# xen_teensy_controls_template.net
KiCad netlist of a schematic drawn in EAGLE
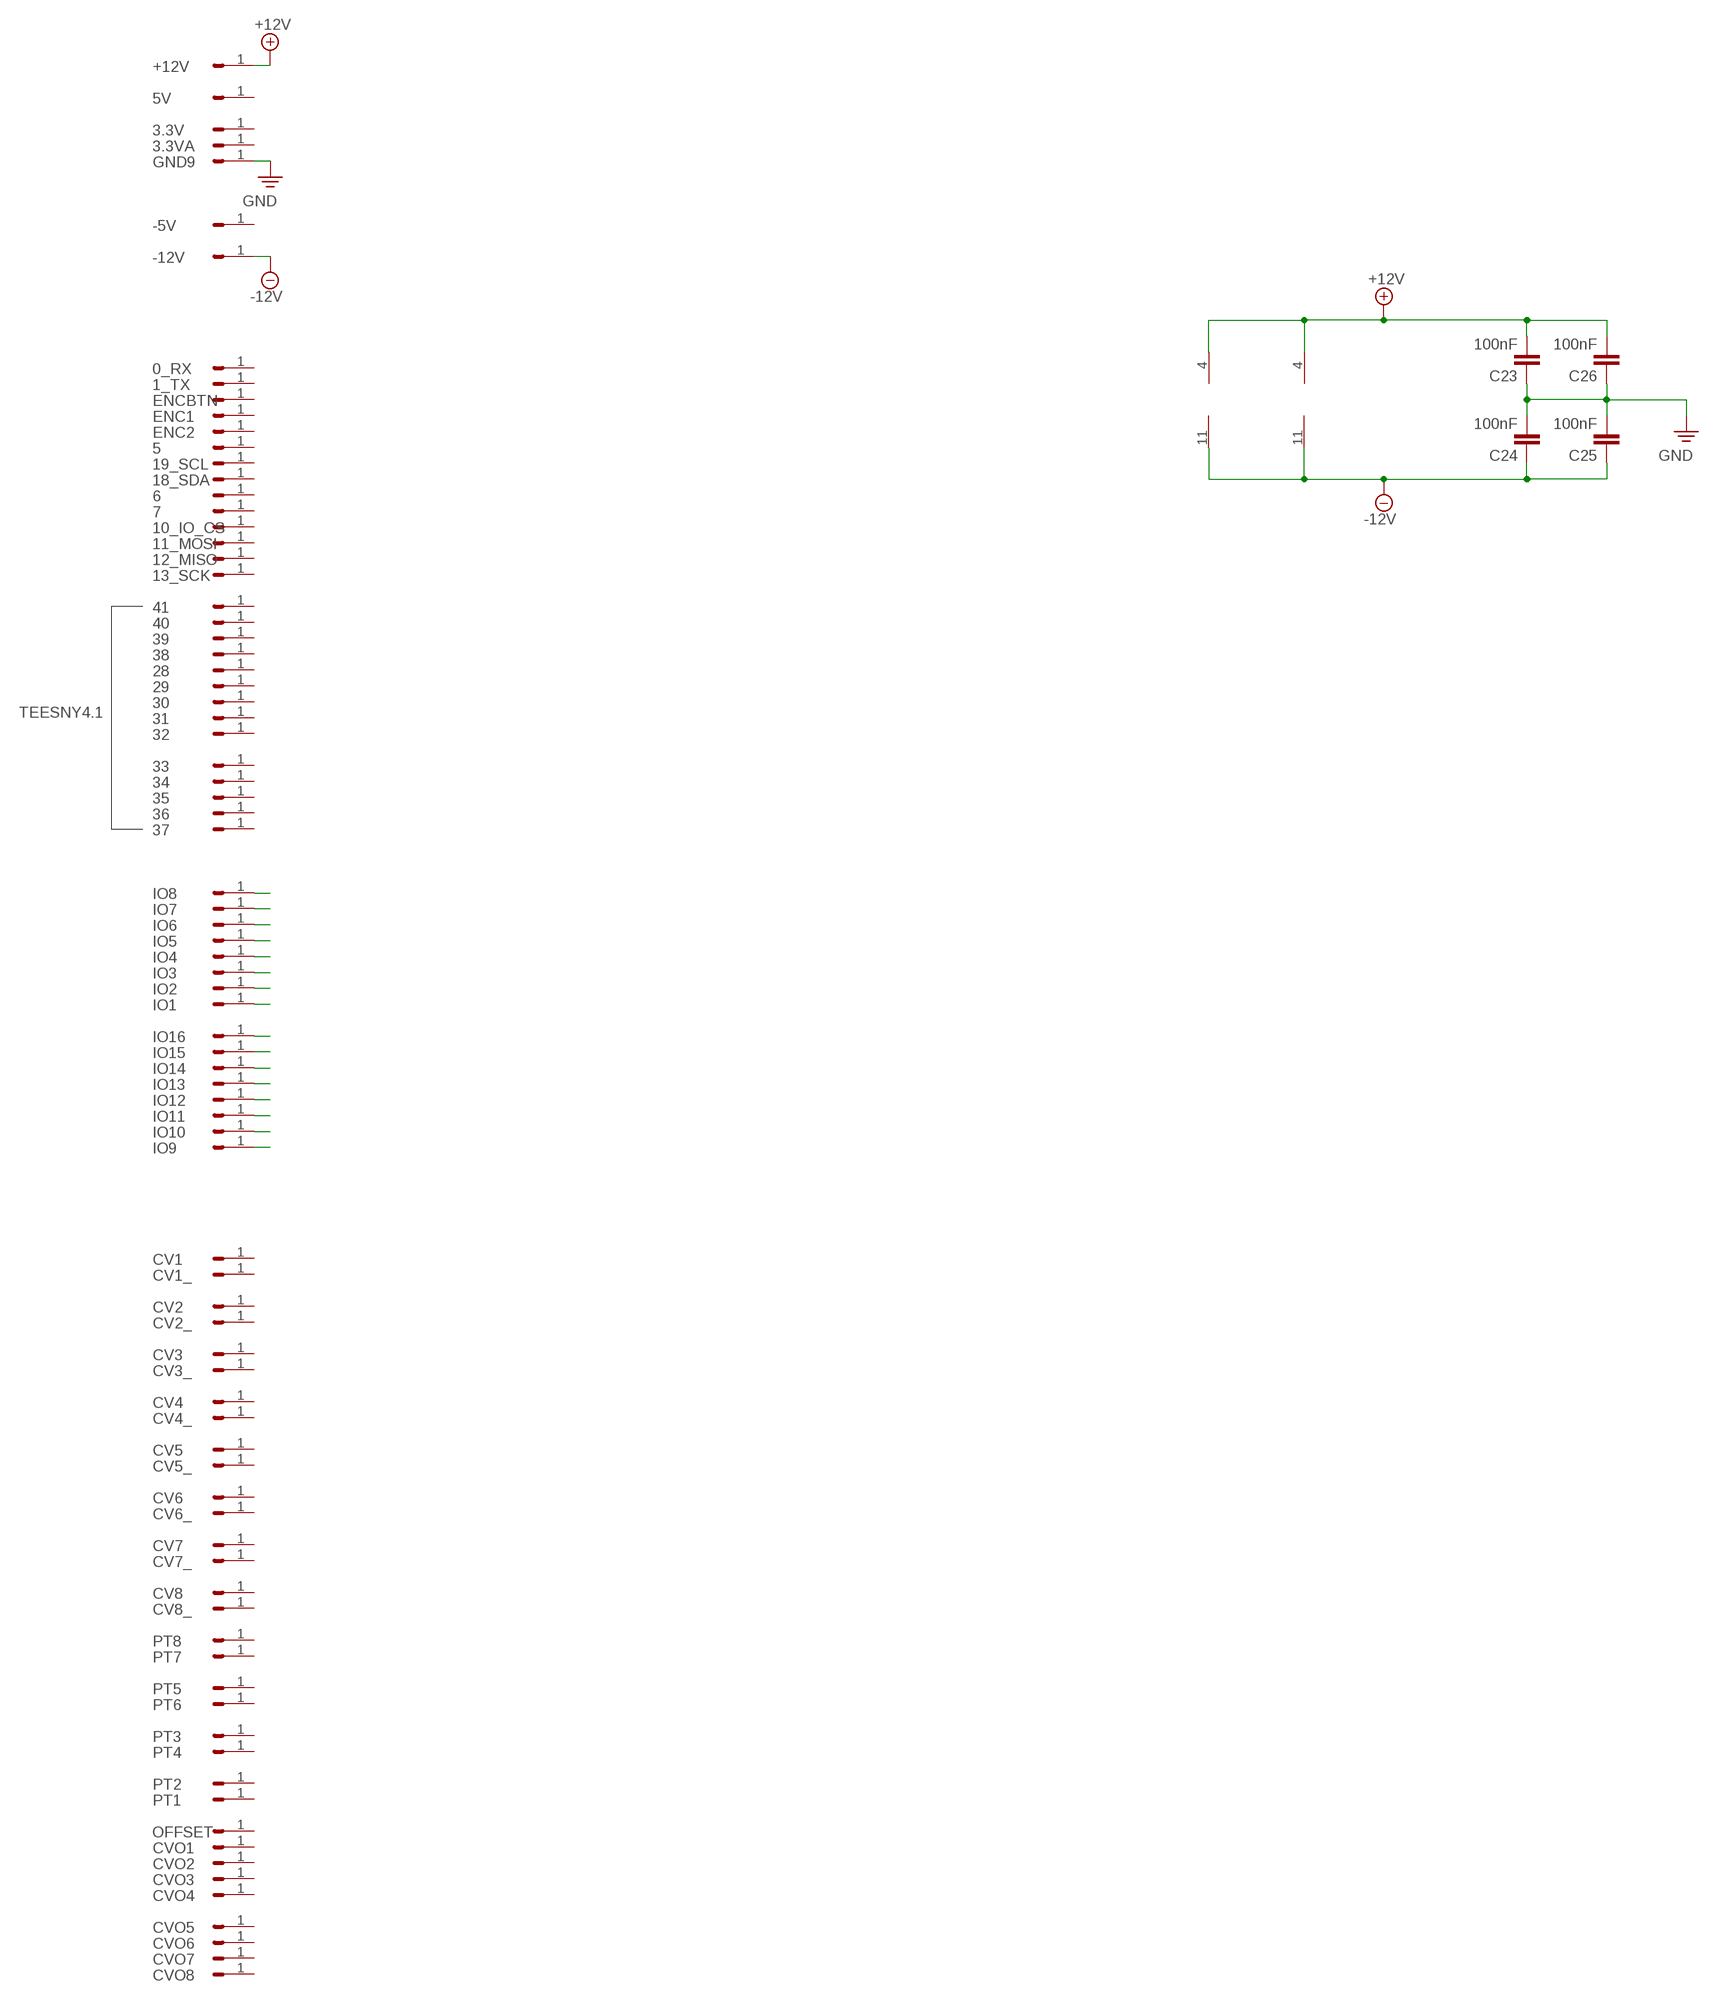
[diagram p0: schematic, sheet 1]

(export (version "E")
  (design (tool "Eeschema 10.0.6"))
  (components
    (comp (ref "+12V")
      (value "HEADER/MALE/01")
      (footprint "eagle-import:HEADER_MALE_01")
      (fields (field (name "SPICEPREFIX") "X"))
      (libsource (lib "eagle-import") (part "HEADER/MALE/01"))
    )
    (comp (ref "-5V")
      (value "HEADER/MALE/01")
      (footprint "eagle-import:HEADER_MALE_01")
      (fields (field (name "SPICEPREFIX") "X"))
      (libsource (lib "eagle-import") (part "HEADER/MALE/01"))
    )
    (comp (ref "-12V")
      (value "HEADER/MALE/01")
      (footprint "eagle-import:HEADER_MALE_01")
      (fields (field (name "SPICEPREFIX") "X"))
      (libsource (lib "eagle-import") (part "HEADER/MALE/01"))
    )
    (comp (ref "0_RX")
      (value "HEADER/MALE/01")
      (footprint "eagle-import:HEADER_MALE_01")
      (fields (field (name "SPICEPREFIX") "X"))
      (libsource (lib "eagle-import") (part "HEADER/MALE/01"))
    )
    (comp (ref "1_TX")
      (value "HEADER/MALE/01")
      (footprint "eagle-import:HEADER_MALE_01")
      (fields (field (name "SPICEPREFIX") "X"))
      (libsource (lib "eagle-import") (part "HEADER/MALE/01"))
    )
    (comp (ref "3.3V")
      (value "HEADER/MALE/01")
      (footprint "eagle-import:HEADER_MALE_01")
      (fields (field (name "SPICEPREFIX") "X"))
      (libsource (lib "eagle-import") (part "HEADER/MALE/01"))
    )
    (comp (ref "3.3VA")
      (value "HEADER/MALE/01")
      (footprint "eagle-import:HEADER_MALE_01")
      (fields (field (name "SPICEPREFIX") "X"))
      (libsource (lib "eagle-import") (part "HEADER/MALE/01"))
    )
    (comp (ref "5")
      (value "HEADER/MALE/01")
      (footprint "eagle-import:HEADER_MALE_01")
      (fields (field (name "SPICEPREFIX") "X"))
      (libsource (lib "eagle-import") (part "HEADER/MALE/01"))
    )
    (comp (ref "5V")
      (value "HEADER/MALE/01")
      (footprint "eagle-import:HEADER_MALE_01")
      (fields (field (name "SPICEPREFIX") "X"))
      (libsource (lib "eagle-import") (part "HEADER/MALE/01"))
    )
    (comp (ref "6")
      (value "HEADER/MALE/01")
      (footprint "eagle-import:HEADER_MALE_01")
      (fields (field (name "SPICEPREFIX") "X"))
      (libsource (lib "eagle-import") (part "HEADER/MALE/01"))
    )
    (comp (ref "7")
      (value "HEADER/MALE/01")
      (footprint "eagle-import:HEADER_MALE_01")
      (fields (field (name "SPICEPREFIX") "X"))
      (libsource (lib "eagle-import") (part "HEADER/MALE/01"))
    )
    (comp (ref "10_IO_CS")
      (value "HEADER/MALE/01")
      (footprint "eagle-import:HEADER_MALE_01")
      (fields (field (name "SPICEPREFIX") "X"))
      (libsource (lib "eagle-import") (part "HEADER/MALE/01"))
    )
    (comp (ref "11_MOSI")
      (value "HEADER/MALE/01")
      (footprint "eagle-import:HEADER_MALE_01")
      (fields (field (name "SPICEPREFIX") "X"))
      (libsource (lib "eagle-import") (part "HEADER/MALE/01"))
    )
    (comp (ref "12_MISO")
      (value "HEADER/MALE/01")
      (footprint "eagle-import:HEADER_MALE_01")
      (fields (field (name "SPICEPREFIX") "X"))
      (libsource (lib "eagle-import") (part "HEADER/MALE/01"))
    )
    (comp (ref "13_SCK")
      (value "HEADER/MALE/01")
      (footprint "eagle-import:HEADER_MALE_01")
      (fields (field (name "SPICEPREFIX") "X"))
      (libsource (lib "eagle-import") (part "HEADER/MALE/01"))
    )
    (comp (ref "18_SDA")
      (value "HEADER/MALE/01")
      (footprint "eagle-import:HEADER_MALE_01")
      (fields (field (name "SPICEPREFIX") "X"))
      (libsource (lib "eagle-import") (part "HEADER/MALE/01"))
    )
    (comp (ref "19_SCL")
      (value "HEADER/MALE/01")
      (footprint "eagle-import:HEADER_MALE_01")
      (fields (field (name "SPICEPREFIX") "X"))
      (libsource (lib "eagle-import") (part "HEADER/MALE/01"))
    )
    (comp (ref "28")
      (value "HEADER/MALE/01")
      (footprint "eagle-import:HEADER_MALE_01")
      (fields (field (name "SPICEPREFIX") "X"))
      (libsource (lib "eagle-import") (part "HEADER/MALE/01"))
    )
    (comp (ref "29")
      (value "HEADER/MALE/01")
      (footprint "eagle-import:HEADER_MALE_01")
      (fields (field (name "SPICEPREFIX") "X"))
      (libsource (lib "eagle-import") (part "HEADER/MALE/01"))
    )
    (comp (ref "30")
      (value "HEADER/MALE/01")
      (footprint "eagle-import:HEADER_MALE_01")
      (fields (field (name "SPICEPREFIX") "X"))
      (libsource (lib "eagle-import") (part "HEADER/MALE/01"))
    )
    (comp (ref "31")
      (value "HEADER/MALE/01")
      (footprint "eagle-import:HEADER_MALE_01")
      (fields (field (name "SPICEPREFIX") "X"))
      (libsource (lib "eagle-import") (part "HEADER/MALE/01"))
    )
    (comp (ref "32")
      (value "HEADER/MALE/01")
      (footprint "eagle-import:HEADER_MALE_01")
      (fields (field (name "SPICEPREFIX") "X"))
      (libsource (lib "eagle-import") (part "HEADER/MALE/01"))
    )
    (comp (ref "33")
      (value "HEADER/MALE/01")
      (footprint "eagle-import:HEADER_MALE_01")
      (fields (field (name "SPICEPREFIX") "X"))
      (libsource (lib "eagle-import") (part "HEADER/MALE/01"))
    )
    (comp (ref "34")
      (value "HEADER/MALE/01")
      (footprint "eagle-import:HEADER_MALE_01")
      (fields (field (name "SPICEPREFIX") "X"))
      (libsource (lib "eagle-import") (part "HEADER/MALE/01"))
    )
    (comp (ref "35")
      (value "HEADER/MALE/01")
      (footprint "eagle-import:HEADER_MALE_01")
      (fields (field (name "SPICEPREFIX") "X"))
      (libsource (lib "eagle-import") (part "HEADER/MALE/01"))
    )
    (comp (ref "36")
      (value "HEADER/MALE/01")
      (footprint "eagle-import:HEADER_MALE_01")
      (fields (field (name "SPICEPREFIX") "X"))
      (libsource (lib "eagle-import") (part "HEADER/MALE/01"))
    )
    (comp (ref "37")
      (value "HEADER/MALE/01")
      (footprint "eagle-import:HEADER_MALE_01")
      (fields (field (name "SPICEPREFIX") "X"))
      (libsource (lib "eagle-import") (part "HEADER/MALE/01"))
    )
    (comp (ref "38")
      (value "HEADER/MALE/01")
      (footprint "eagle-import:HEADER_MALE_01")
      (fields (field (name "SPICEPREFIX") "X"))
      (libsource (lib "eagle-import") (part "HEADER/MALE/01"))
    )
    (comp (ref "39")
      (value "HEADER/MALE/01")
      (footprint "eagle-import:HEADER_MALE_01")
      (fields (field (name "SPICEPREFIX") "X"))
      (libsource (lib "eagle-import") (part "HEADER/MALE/01"))
    )
    (comp (ref "40")
      (value "HEADER/MALE/01")
      (footprint "eagle-import:HEADER_MALE_01")
      (fields (field (name "SPICEPREFIX") "X"))
      (libsource (lib "eagle-import") (part "HEADER/MALE/01"))
    )
    (comp (ref "41")
      (value "HEADER/MALE/01")
      (footprint "eagle-import:HEADER_MALE_01")
      (fields (field (name "SPICEPREFIX") "X"))
      (libsource (lib "eagle-import") (part "HEADER/MALE/01"))
    )
    (comp (ref "C23")
      (value "100nF")
      (footprint "eagle-import:C0603")
      (libsource (lib "eagle-import") (part "CAPACITORC0603"))
    )
    (comp (ref "C24")
      (value "100nF")
      (footprint "eagle-import:C0603")
      (libsource (lib "eagle-import") (part "CAPACITORC0603"))
    )
    (comp (ref "C25")
      (value "100nF")
      (footprint "eagle-import:C0603")
      (libsource (lib "eagle-import") (part "CAPACITORC0603"))
    )
    (comp (ref "C26")
      (value "100nF")
      (footprint "eagle-import:C0603")
      (libsource (lib "eagle-import") (part "CAPACITORC0603"))
    )
    (comp (ref "CV1")
      (value "HEADER/MALE/01")
      (footprint "eagle-import:HEADER_MALE_01")
      (fields (field (name "SPICEPREFIX") "X"))
      (libsource (lib "eagle-import") (part "HEADER/MALE/01"))
    )
    (comp (ref "CV1_")
      (value "HEADER/MALE/01")
      (footprint "eagle-import:HEADER_MALE_01")
      (fields (field (name "SPICEPREFIX") "X"))
      (libsource (lib "eagle-import") (part "HEADER/MALE/01"))
    )
    (comp (ref "CV2")
      (value "HEADER/MALE/01")
      (footprint "eagle-import:HEADER_MALE_01")
      (fields (field (name "SPICEPREFIX") "X"))
      (libsource (lib "eagle-import") (part "HEADER/MALE/01"))
    )
    (comp (ref "CV2_")
      (value "HEADER/MALE/01")
      (footprint "eagle-import:HEADER_MALE_01")
      (fields (field (name "SPICEPREFIX") "X"))
      (libsource (lib "eagle-import") (part "HEADER/MALE/01"))
    )
    (comp (ref "CV3")
      (value "HEADER/MALE/01")
      (footprint "eagle-import:HEADER_MALE_01")
      (fields (field (name "SPICEPREFIX") "X"))
      (libsource (lib "eagle-import") (part "HEADER/MALE/01"))
    )
    (comp (ref "CV3_")
      (value "HEADER/MALE/01")
      (footprint "eagle-import:HEADER_MALE_01")
      (fields (field (name "SPICEPREFIX") "X"))
      (libsource (lib "eagle-import") (part "HEADER/MALE/01"))
    )
    (comp (ref "CV4")
      (value "HEADER/MALE/01")
      (footprint "eagle-import:HEADER_MALE_01")
      (fields (field (name "SPICEPREFIX") "X"))
      (libsource (lib "eagle-import") (part "HEADER/MALE/01"))
    )
    (comp (ref "CV4_")
      (value "HEADER/MALE/01")
      (footprint "eagle-import:HEADER_MALE_01")
      (fields (field (name "SPICEPREFIX") "X"))
      (libsource (lib "eagle-import") (part "HEADER/MALE/01"))
    )
    (comp (ref "CV5")
      (value "HEADER/MALE/01")
      (footprint "eagle-import:HEADER_MALE_01")
      (fields (field (name "SPICEPREFIX") "X"))
      (libsource (lib "eagle-import") (part "HEADER/MALE/01"))
    )
    (comp (ref "CV5_")
      (value "HEADER/MALE/01")
      (footprint "eagle-import:HEADER_MALE_01")
      (fields (field (name "SPICEPREFIX") "X"))
      (libsource (lib "eagle-import") (part "HEADER/MALE/01"))
    )
    (comp (ref "CV6")
      (value "HEADER/MALE/01")
      (footprint "eagle-import:HEADER_MALE_01")
      (fields (field (name "SPICEPREFIX") "X"))
      (libsource (lib "eagle-import") (part "HEADER/MALE/01"))
    )
    (comp (ref "CV6_")
      (value "HEADER/MALE/01")
      (footprint "eagle-import:HEADER_MALE_01")
      (fields (field (name "SPICEPREFIX") "X"))
      (libsource (lib "eagle-import") (part "HEADER/MALE/01"))
    )
    (comp (ref "CV7")
      (value "HEADER/MALE/01")
      (footprint "eagle-import:HEADER_MALE_01")
      (fields (field (name "SPICEPREFIX") "X"))
      (libsource (lib "eagle-import") (part "HEADER/MALE/01"))
    )
    (comp (ref "CV7_")
      (value "HEADER/MALE/01")
      (footprint "eagle-import:HEADER_MALE_01")
      (fields (field (name "SPICEPREFIX") "X"))
      (libsource (lib "eagle-import") (part "HEADER/MALE/01"))
    )
    (comp (ref "CV8")
      (value "HEADER/MALE/01")
      (footprint "eagle-import:HEADER_MALE_01")
      (fields (field (name "SPICEPREFIX") "X"))
      (libsource (lib "eagle-import") (part "HEADER/MALE/01"))
    )
    (comp (ref "CV8_")
      (value "HEADER/MALE/01")
      (footprint "eagle-import:HEADER_MALE_01")
      (fields (field (name "SPICEPREFIX") "X"))
      (libsource (lib "eagle-import") (part "HEADER/MALE/01"))
    )
    (comp (ref "CVO1")
      (value "HEADER/MALE/01")
      (footprint "eagle-import:HEADER_MALE_01")
      (fields (field (name "SPICEPREFIX") "X"))
      (libsource (lib "eagle-import") (part "HEADER/MALE/01"))
    )
    (comp (ref "CVO2")
      (value "HEADER/MALE/01")
      (footprint "eagle-import:HEADER_MALE_01")
      (fields (field (name "SPICEPREFIX") "X"))
      (libsource (lib "eagle-import") (part "HEADER/MALE/01"))
    )
    (comp (ref "CVO3")
      (value "HEADER/MALE/01")
      (footprint "eagle-import:HEADER_MALE_01")
      (fields (field (name "SPICEPREFIX") "X"))
      (libsource (lib "eagle-import") (part "HEADER/MALE/01"))
    )
    (comp (ref "CVO4")
      (value "HEADER/MALE/01")
      (footprint "eagle-import:HEADER_MALE_01")
      (fields (field (name "SPICEPREFIX") "X"))
      (libsource (lib "eagle-import") (part "HEADER/MALE/01"))
    )
    (comp (ref "CVO5")
      (value "HEADER/MALE/01")
      (footprint "eagle-import:HEADER_MALE_01")
      (fields (field (name "SPICEPREFIX") "X"))
      (libsource (lib "eagle-import") (part "HEADER/MALE/01"))
    )
    (comp (ref "CVO6")
      (value "HEADER/MALE/01")
      (footprint "eagle-import:HEADER_MALE_01")
      (fields (field (name "SPICEPREFIX") "X"))
      (libsource (lib "eagle-import") (part "HEADER/MALE/01"))
    )
    (comp (ref "CVO7")
      (value "HEADER/MALE/01")
      (footprint "eagle-import:HEADER_MALE_01")
      (fields (field (name "SPICEPREFIX") "X"))
      (libsource (lib "eagle-import") (part "HEADER/MALE/01"))
    )
    (comp (ref "CVO8")
      (value "HEADER/MALE/01")
      (footprint "eagle-import:HEADER_MALE_01")
      (fields (field (name "SPICEPREFIX") "X"))
      (libsource (lib "eagle-import") (part "HEADER/MALE/01"))
    )
    (comp (ref "ENC1")
      (value "HEADER/MALE/01")
      (footprint "eagle-import:HEADER_MALE_01")
      (fields (field (name "SPICEPREFIX") "X"))
      (libsource (lib "eagle-import") (part "HEADER/MALE/01"))
    )
    (comp (ref "ENC2")
      (value "HEADER/MALE/01")
      (footprint "eagle-import:HEADER_MALE_01")
      (fields (field (name "SPICEPREFIX") "X"))
      (libsource (lib "eagle-import") (part "HEADER/MALE/01"))
    )
    (comp (ref "ENCBTN")
      (value "HEADER/MALE/01")
      (footprint "eagle-import:HEADER_MALE_01")
      (fields (field (name "SPICEPREFIX") "X"))
      (libsource (lib "eagle-import") (part "HEADER/MALE/01"))
    )
    (comp (ref "GND9")
      (value "HEADER/MALE/01")
      (footprint "eagle-import:HEADER_MALE_01")
      (fields (field (name "SPICEPREFIX") "X"))
      (libsource (lib "eagle-import") (part "HEADER/MALE/01"))
    )
    (comp (ref "IC1")
      (value "TL074D")
      (footprint "eagle-import:SO14")
      (libsource (lib "eagle-import") (part "TL074D"))
    )
    (comp (ref "IC5")
      (value "TL074D")
      (footprint "eagle-import:SO14")
      (libsource (lib "eagle-import") (part "TL074D"))
    )
    (comp (ref "IO1")
      (value "HEADER/MALE/01")
      (footprint "eagle-import:HEADER_MALE_01")
      (fields (field (name "SPICEPREFIX") "X"))
      (libsource (lib "eagle-import") (part "HEADER/MALE/01"))
    )
    (comp (ref "IO2")
      (value "HEADER/MALE/01")
      (footprint "eagle-import:HEADER_MALE_01")
      (fields (field (name "SPICEPREFIX") "X"))
      (libsource (lib "eagle-import") (part "HEADER/MALE/01"))
    )
    (comp (ref "IO3")
      (value "HEADER/MALE/01")
      (footprint "eagle-import:HEADER_MALE_01")
      (fields (field (name "SPICEPREFIX") "X"))
      (libsource (lib "eagle-import") (part "HEADER/MALE/01"))
    )
    (comp (ref "IO4")
      (value "HEADER/MALE/01")
      (footprint "eagle-import:HEADER_MALE_01")
      (fields (field (name "SPICEPREFIX") "X"))
      (libsource (lib "eagle-import") (part "HEADER/MALE/01"))
    )
    (comp (ref "IO5")
      (value "HEADER/MALE/01")
      (footprint "eagle-import:HEADER_MALE_01")
      (fields (field (name "SPICEPREFIX") "X"))
      (libsource (lib "eagle-import") (part "HEADER/MALE/01"))
    )
    (comp (ref "IO6")
      (value "HEADER/MALE/01")
      (footprint "eagle-import:HEADER_MALE_01")
      (fields (field (name "SPICEPREFIX") "X"))
      (libsource (lib "eagle-import") (part "HEADER/MALE/01"))
    )
    (comp (ref "IO7")
      (value "HEADER/MALE/01")
      (footprint "eagle-import:HEADER_MALE_01")
      (fields (field (name "SPICEPREFIX") "X"))
      (libsource (lib "eagle-import") (part "HEADER/MALE/01"))
    )
    (comp (ref "IO8")
      (value "HEADER/MALE/01")
      (footprint "eagle-import:HEADER_MALE_01")
      (fields (field (name "SPICEPREFIX") "X"))
      (libsource (lib "eagle-import") (part "HEADER/MALE/01"))
    )
    (comp (ref "IO9")
      (value "HEADER/MALE/01")
      (footprint "eagle-import:HEADER_MALE_01")
      (fields (field (name "SPICEPREFIX") "X"))
      (libsource (lib "eagle-import") (part "HEADER/MALE/01"))
    )
    (comp (ref "IO10")
      (value "HEADER/MALE/01")
      (footprint "eagle-import:HEADER_MALE_01")
      (fields (field (name "SPICEPREFIX") "X"))
      (libsource (lib "eagle-import") (part "HEADER/MALE/01"))
    )
    (comp (ref "IO11")
      (value "HEADER/MALE/01")
      (footprint "eagle-import:HEADER_MALE_01")
      (fields (field (name "SPICEPREFIX") "X"))
      (libsource (lib "eagle-import") (part "HEADER/MALE/01"))
    )
    (comp (ref "IO12")
      (value "HEADER/MALE/01")
      (footprint "eagle-import:HEADER_MALE_01")
      (fields (field (name "SPICEPREFIX") "X"))
      (libsource (lib "eagle-import") (part "HEADER/MALE/01"))
    )
    (comp (ref "IO13")
      (value "HEADER/MALE/01")
      (footprint "eagle-import:HEADER_MALE_01")
      (fields (field (name "SPICEPREFIX") "X"))
      (libsource (lib "eagle-import") (part "HEADER/MALE/01"))
    )
    (comp (ref "IO14")
      (value "HEADER/MALE/01")
      (footprint "eagle-import:HEADER_MALE_01")
      (fields (field (name "SPICEPREFIX") "X"))
      (libsource (lib "eagle-import") (part "HEADER/MALE/01"))
    )
    (comp (ref "IO15")
      (value "HEADER/MALE/01")
      (footprint "eagle-import:HEADER_MALE_01")
      (fields (field (name "SPICEPREFIX") "X"))
      (libsource (lib "eagle-import") (part "HEADER/MALE/01"))
    )
    (comp (ref "IO16")
      (value "HEADER/MALE/01")
      (footprint "eagle-import:HEADER_MALE_01")
      (fields (field (name "SPICEPREFIX") "X"))
      (libsource (lib "eagle-import") (part "HEADER/MALE/01"))
    )
    (comp (ref "OFFSET")
      (value "HEADER/MALE/01")
      (footprint "eagle-import:HEADER_MALE_01")
      (fields (field (name "SPICEPREFIX") "X"))
      (libsource (lib "eagle-import") (part "HEADER/MALE/01"))
    )
    (comp (ref "PT1")
      (value "HEADER/MALE/01")
      (footprint "eagle-import:HEADER_MALE_01")
      (fields (field (name "SPICEPREFIX") "X"))
      (libsource (lib "eagle-import") (part "HEADER/MALE/01"))
    )
    (comp (ref "PT2")
      (value "HEADER/MALE/01")
      (footprint "eagle-import:HEADER_MALE_01")
      (fields (field (name "SPICEPREFIX") "X"))
      (libsource (lib "eagle-import") (part "HEADER/MALE/01"))
    )
    (comp (ref "PT3")
      (value "HEADER/MALE/01")
      (footprint "eagle-import:HEADER_MALE_01")
      (fields (field (name "SPICEPREFIX") "X"))
      (libsource (lib "eagle-import") (part "HEADER/MALE/01"))
    )
    (comp (ref "PT4")
      (value "HEADER/MALE/01")
      (footprint "eagle-import:HEADER_MALE_01")
      (fields (field (name "SPICEPREFIX") "X"))
      (libsource (lib "eagle-import") (part "HEADER/MALE/01"))
    )
    (comp (ref "PT5")
      (value "HEADER/MALE/01")
      (footprint "eagle-import:HEADER_MALE_01")
      (fields (field (name "SPICEPREFIX") "X"))
      (libsource (lib "eagle-import") (part "HEADER/MALE/01"))
    )
    (comp (ref "PT6")
      (value "HEADER/MALE/01")
      (footprint "eagle-import:HEADER_MALE_01")
      (fields (field (name "SPICEPREFIX") "X"))
      (libsource (lib "eagle-import") (part "HEADER/MALE/01"))
    )
    (comp (ref "PT7")
      (value "HEADER/MALE/01")
      (footprint "eagle-import:HEADER_MALE_01")
      (fields (field (name "SPICEPREFIX") "X"))
      (libsource (lib "eagle-import") (part "HEADER/MALE/01"))
    )
    (comp (ref "PT8")
      (value "HEADER/MALE/01")
      (footprint "eagle-import:HEADER_MALE_01")
      (fields (field (name "SPICEPREFIX") "X"))
      (libsource (lib "eagle-import") (part "HEADER/MALE/01"))
    )
  )
  (nets
    (net (code "1") (name "+12V") (class "Default")
      (node (ref "+12V") (pin "1") (pinfunction "3_1") (pintype "passive"))
      (node (ref "C23") (pin "2") (pinfunction "2_2") (pintype "passive"))
      (node (ref "C26") (pin "2") (pinfunction "2_2") (pintype "passive"))
      (node (ref "IC1") (pin "4") (pinfunction "V+_4") (pintype "power_in"))
      (node (ref "IC5") (pin "4") (pinfunction "V+_4") (pintype "power_in"))
    )
    (net (code "2") (name "-12V") (class "Default")
      (node (ref "-12V") (pin "1") (pinfunction "3_1") (pintype "passive"))
      (node (ref "C24") (pin "1") (pinfunction "1_1") (pintype "passive"))
      (node (ref "C25") (pin "1") (pinfunction "1_1") (pintype "passive"))
      (node (ref "IC1") (pin "11") (pinfunction "V-_11") (pintype "power_in"))
      (node (ref "IC5") (pin "11") (pinfunction "V-_11") (pintype "power_in"))
    )
    (net (code "3") (name "GND") (class "Default")
      (node (ref "C23") (pin "1") (pinfunction "1_1") (pintype "passive"))
      (node (ref "C24") (pin "2") (pinfunction "2_2") (pintype "passive"))
      (node (ref "C25") (pin "2") (pinfunction "2_2") (pintype "passive"))
      (node (ref "C26") (pin "1") (pinfunction "1_1") (pintype "passive"))
      (node (ref "GND9") (pin "1") (pinfunction "3_1") (pintype "passive"))
    )
    (net (code "4") (name "unconnected-(-5V-3-Pad1)") (class "Default")
      (node (ref "-5V") (pin "1") (pinfunction "3_1") (pintype "passive"))
    )
    (net (code "5") (name "unconnected-(0_RX-3-Pad1)") (class "Default")
      (node (ref "0_RX") (pin "1") (pinfunction "3_1") (pintype "passive"))
    )
    (net (code "6") (name "unconnected-(1_TX-3-Pad1)") (class "Default")
      (node (ref "1_TX") (pin "1") (pinfunction "3_1") (pintype "passive"))
    )
    (net (code "7") (name "unconnected-(3.3V-3-Pad1)") (class "Default")
      (node (ref "3.3V") (pin "1") (pinfunction "3_1") (pintype "passive"))
    )
    (net (code "8") (name "unconnected-(3.3VA-3-Pad1)") (class "Default")
      (node (ref "3.3VA") (pin "1") (pinfunction "3_1") (pintype "passive"))
    )
    (net (code "9") (name "unconnected-(5-3-Pad1)") (class "Default")
      (node (ref "5") (pin "1") (pinfunction "3_1") (pintype "passive"))
    )
    (net (code "10") (name "unconnected-(5V-3-Pad1)") (class "Default")
      (node (ref "5V") (pin "1") (pinfunction "3_1") (pintype "passive"))
    )
    (net (code "11") (name "unconnected-(6-3-Pad1)") (class "Default")
      (node (ref "6") (pin "1") (pinfunction "3_1") (pintype "passive"))
    )
    (net (code "12") (name "unconnected-(7-3-Pad1)") (class "Default")
      (node (ref "7") (pin "1") (pinfunction "3_1") (pintype "passive"))
    )
    (net (code "13") (name "unconnected-(10_IO_CS-3-Pad1)") (class "Default")
      (node (ref "10_IO_CS") (pin "1") (pinfunction "3_1") (pintype "passive"))
    )
    (net (code "14") (name "unconnected-(11_MOSI-3-Pad1)") (class "Default")
      (node (ref "11_MOSI") (pin "1") (pinfunction "3_1") (pintype "passive"))
    )
    (net (code "15") (name "unconnected-(12_MISO-3-Pad1)") (class "Default")
      (node (ref "12_MISO") (pin "1") (pinfunction "3_1") (pintype "passive"))
    )
    (net (code "16") (name "unconnected-(13_SCK-3-Pad1)") (class "Default")
      (node (ref "13_SCK") (pin "1") (pinfunction "3_1") (pintype "passive"))
    )
    (net (code "17") (name "unconnected-(18_SDA-3-Pad1)") (class "Default")
      (node (ref "18_SDA") (pin "1") (pinfunction "3_1") (pintype "passive"))
    )
    (net (code "18") (name "unconnected-(19_SCL-3-Pad1)") (class "Default")
      (node (ref "19_SCL") (pin "1") (pinfunction "3_1") (pintype "passive"))
    )
    (net (code "19") (name "unconnected-(28-3-Pad1)") (class "Default")
      (node (ref "28") (pin "1") (pinfunction "3_1") (pintype "passive"))
    )
    (net (code "20") (name "unconnected-(29-3-Pad1)") (class "Default")
      (node (ref "29") (pin "1") (pinfunction "3_1") (pintype "passive"))
    )
    (net (code "21") (name "unconnected-(30-3-Pad1)") (class "Default")
      (node (ref "30") (pin "1") (pinfunction "3_1") (pintype "passive"))
    )
    (net (code "22") (name "unconnected-(31-3-Pad1)") (class "Default")
      (node (ref "31") (pin "1") (pinfunction "3_1") (pintype "passive"))
    )
    (net (code "23") (name "unconnected-(32-3-Pad1)") (class "Default")
      (node (ref "32") (pin "1") (pinfunction "3_1") (pintype "passive"))
    )
    (net (code "24") (name "unconnected-(33-3-Pad1)") (class "Default")
      (node (ref "33") (pin "1") (pinfunction "3_1") (pintype "passive"))
    )
    (net (code "25") (name "unconnected-(34-3-Pad1)") (class "Default")
      (node (ref "34") (pin "1") (pinfunction "3_1") (pintype "passive"))
    )
    (net (code "26") (name "unconnected-(35-3-Pad1)") (class "Default")
      (node (ref "35") (pin "1") (pinfunction "3_1") (pintype "passive"))
    )
    (net (code "27") (name "unconnected-(36-3-Pad1)") (class "Default")
      (node (ref "36") (pin "1") (pinfunction "3_1") (pintype "passive"))
    )
    (net (code "28") (name "unconnected-(37-3-Pad1)") (class "Default")
      (node (ref "37") (pin "1") (pinfunction "3_1") (pintype "passive"))
    )
    (net (code "29") (name "unconnected-(38-3-Pad1)") (class "Default")
      (node (ref "38") (pin "1") (pinfunction "3_1") (pintype "passive"))
    )
    (net (code "30") (name "unconnected-(39-3-Pad1)") (class "Default")
      (node (ref "39") (pin "1") (pinfunction "3_1") (pintype "passive"))
    )
    (net (code "31") (name "unconnected-(40-3-Pad1)") (class "Default")
      (node (ref "40") (pin "1") (pinfunction "3_1") (pintype "passive"))
    )
    (net (code "32") (name "unconnected-(41-3-Pad1)") (class "Default")
      (node (ref "41") (pin "1") (pinfunction "3_1") (pintype "passive"))
    )
    (net (code "33") (name "unconnected-(CV1-3-Pad1)") (class "Default")
      (node (ref "CV1") (pin "1") (pinfunction "3_1") (pintype "passive"))
    )
    (net (code "34") (name "unconnected-(CV1_-3-Pad1)") (class "Default")
      (node (ref "CV1_") (pin "1") (pinfunction "3_1") (pintype "passive"))
    )
    (net (code "35") (name "unconnected-(CV2-3-Pad1)") (class "Default")
      (node (ref "CV2") (pin "1") (pinfunction "3_1") (pintype "passive"))
    )
    (net (code "36") (name "unconnected-(CV2_-3-Pad1)") (class "Default")
      (node (ref "CV2_") (pin "1") (pinfunction "3_1") (pintype "passive"))
    )
    (net (code "37") (name "unconnected-(CV3-3-Pad1)") (class "Default")
      (node (ref "CV3") (pin "1") (pinfunction "3_1") (pintype "passive"))
    )
    (net (code "38") (name "unconnected-(CV3_-3-Pad1)") (class "Default")
      (node (ref "CV3_") (pin "1") (pinfunction "3_1") (pintype "passive"))
    )
    (net (code "39") (name "unconnected-(CV4-3-Pad1)") (class "Default")
      (node (ref "CV4") (pin "1") (pinfunction "3_1") (pintype "passive"))
    )
    (net (code "40") (name "unconnected-(CV4_-3-Pad1)") (class "Default")
      (node (ref "CV4_") (pin "1") (pinfunction "3_1") (pintype "passive"))
    )
    (net (code "41") (name "unconnected-(CV5-3-Pad1)") (class "Default")
      (node (ref "CV5") (pin "1") (pinfunction "3_1") (pintype "passive"))
    )
    (net (code "42") (name "unconnected-(CV5_-3-Pad1)") (class "Default")
      (node (ref "CV5_") (pin "1") (pinfunction "3_1") (pintype "passive"))
    )
    (net (code "43") (name "unconnected-(CV6-3-Pad1)") (class "Default")
      (node (ref "CV6") (pin "1") (pinfunction "3_1") (pintype "passive"))
    )
    (net (code "44") (name "unconnected-(CV6_-3-Pad1)") (class "Default")
      (node (ref "CV6_") (pin "1") (pinfunction "3_1") (pintype "passive"))
    )
    (net (code "45") (name "unconnected-(CV7-3-Pad1)") (class "Default")
      (node (ref "CV7") (pin "1") (pinfunction "3_1") (pintype "passive"))
    )
    (net (code "46") (name "unconnected-(CV7_-3-Pad1)") (class "Default")
      (node (ref "CV7_") (pin "1") (pinfunction "3_1") (pintype "passive"))
    )
    (net (code "47") (name "unconnected-(CV8-3-Pad1)") (class "Default")
      (node (ref "CV8") (pin "1") (pinfunction "3_1") (pintype "passive"))
    )
    (net (code "48") (name "unconnected-(CV8_-3-Pad1)") (class "Default")
      (node (ref "CV8_") (pin "1") (pinfunction "3_1") (pintype "passive"))
    )
    (net (code "49") (name "unconnected-(CVO1-3-Pad1)") (class "Default")
      (node (ref "CVO1") (pin "1") (pinfunction "3_1") (pintype "passive"))
    )
    (net (code "50") (name "unconnected-(CVO2-3-Pad1)") (class "Default")
      (node (ref "CVO2") (pin "1") (pinfunction "3_1") (pintype "passive"))
    )
    (net (code "51") (name "unconnected-(CVO3-3-Pad1)") (class "Default")
      (node (ref "CVO3") (pin "1") (pinfunction "3_1") (pintype "passive"))
    )
    (net (code "52") (name "unconnected-(CVO4-3-Pad1)") (class "Default")
      (node (ref "CVO4") (pin "1") (pinfunction "3_1") (pintype "passive"))
    )
    (net (code "53") (name "unconnected-(CVO5-3-Pad1)") (class "Default")
      (node (ref "CVO5") (pin "1") (pinfunction "3_1") (pintype "passive"))
    )
    (net (code "54") (name "unconnected-(CVO6-3-Pad1)") (class "Default")
      (node (ref "CVO6") (pin "1") (pinfunction "3_1") (pintype "passive"))
    )
    (net (code "55") (name "unconnected-(CVO7-3-Pad1)") (class "Default")
      (node (ref "CVO7") (pin "1") (pinfunction "3_1") (pintype "passive"))
    )
    (net (code "56") (name "unconnected-(CVO8-3-Pad1)") (class "Default")
      (node (ref "CVO8") (pin "1") (pinfunction "3_1") (pintype "passive"))
    )
    (net (code "57") (name "unconnected-(ENC1-3-Pad1)") (class "Default")
      (node (ref "ENC1") (pin "1") (pinfunction "3_1") (pintype "passive"))
    )
    (net (code "58") (name "unconnected-(ENC2-3-Pad1)") (class "Default")
      (node (ref "ENC2") (pin "1") (pinfunction "3_1") (pintype "passive"))
    )
    (net (code "59") (name "unconnected-(ENCBTN-3-Pad1)") (class "Default")
      (node (ref "ENCBTN") (pin "1") (pinfunction "3_1") (pintype "passive"))
    )
    (net (code "60") (name "unconnected-(IO1-3-Pad1)") (class "Default")
      (node (ref "IO1") (pin "1") (pinfunction "3_1") (pintype "passive"))
    )
    (net (code "61") (name "unconnected-(IO2-3-Pad1)") (class "Default")
      (node (ref "IO2") (pin "1") (pinfunction "3_1") (pintype "passive"))
    )
    (net (code "62") (name "unconnected-(IO3-3-Pad1)") (class "Default")
      (node (ref "IO3") (pin "1") (pinfunction "3_1") (pintype "passive"))
    )
    (net (code "63") (name "unconnected-(IO4-3-Pad1)") (class "Default")
      (node (ref "IO4") (pin "1") (pinfunction "3_1") (pintype "passive"))
    )
    (net (code "64") (name "unconnected-(IO5-3-Pad1)") (class "Default")
      (node (ref "IO5") (pin "1") (pinfunction "3_1") (pintype "passive"))
    )
    (net (code "65") (name "unconnected-(IO6-3-Pad1)") (class "Default")
      (node (ref "IO6") (pin "1") (pinfunction "3_1") (pintype "passive"))
    )
    (net (code "66") (name "unconnected-(IO7-3-Pad1)") (class "Default")
      (node (ref "IO7") (pin "1") (pinfunction "3_1") (pintype "passive"))
    )
    (net (code "67") (name "unconnected-(IO8-3-Pad1)") (class "Default")
      (node (ref "IO8") (pin "1") (pinfunction "3_1") (pintype "passive"))
    )
    (net (code "68") (name "unconnected-(IO9-3-Pad1)") (class "Default")
      (node (ref "IO9") (pin "1") (pinfunction "3_1") (pintype "passive"))
    )
    (net (code "69") (name "unconnected-(IO10-3-Pad1)") (class "Default")
      (node (ref "IO10") (pin "1") (pinfunction "3_1") (pintype "passive"))
    )
    (net (code "70") (name "unconnected-(IO11-3-Pad1)") (class "Default")
      (node (ref "IO11") (pin "1") (pinfunction "3_1") (pintype "passive"))
    )
    (net (code "71") (name "unconnected-(IO12-3-Pad1)") (class "Default")
      (node (ref "IO12") (pin "1") (pinfunction "3_1") (pintype "passive"))
    )
    (net (code "72") (name "unconnected-(IO13-3-Pad1)") (class "Default")
      (node (ref "IO13") (pin "1") (pinfunction "3_1") (pintype "passive"))
    )
    (net (code "73") (name "unconnected-(IO14-3-Pad1)") (class "Default")
      (node (ref "IO14") (pin "1") (pinfunction "3_1") (pintype "passive"))
    )
    (net (code "74") (name "unconnected-(IO15-3-Pad1)") (class "Default")
      (node (ref "IO15") (pin "1") (pinfunction "3_1") (pintype "passive"))
    )
    (net (code "75") (name "unconnected-(IO16-3-Pad1)") (class "Default")
      (node (ref "IO16") (pin "1") (pinfunction "3_1") (pintype "passive"))
    )
    (net (code "76") (name "unconnected-(OFFSET-3-Pad1)") (class "Default")
      (node (ref "OFFSET") (pin "1") (pinfunction "3_1") (pintype "passive"))
    )
    (net (code "77") (name "unconnected-(PT1-3-Pad1)") (class "Default")
      (node (ref "PT1") (pin "1") (pinfunction "3_1") (pintype "passive"))
    )
    (net (code "78") (name "unconnected-(PT2-3-Pad1)") (class "Default")
      (node (ref "PT2") (pin "1") (pinfunction "3_1") (pintype "passive"))
    )
    (net (code "79") (name "unconnected-(PT3-3-Pad1)") (class "Default")
      (node (ref "PT3") (pin "1") (pinfunction "3_1") (pintype "passive"))
    )
    (net (code "80") (name "unconnected-(PT4-3-Pad1)") (class "Default")
      (node (ref "PT4") (pin "1") (pinfunction "3_1") (pintype "passive"))
    )
    (net (code "81") (name "unconnected-(PT5-3-Pad1)") (class "Default")
      (node (ref "PT5") (pin "1") (pinfunction "3_1") (pintype "passive"))
    )
    (net (code "82") (name "unconnected-(PT6-3-Pad1)") (class "Default")
      (node (ref "PT6") (pin "1") (pinfunction "3_1") (pintype "passive"))
    )
    (net (code "83") (name "unconnected-(PT7-3-Pad1)") (class "Default")
      (node (ref "PT7") (pin "1") (pinfunction "3_1") (pintype "passive"))
    )
    (net (code "84") (name "unconnected-(PT8-3-Pad1)") (class "Default")
      (node (ref "PT8") (pin "1") (pinfunction "3_1") (pintype "passive"))
    )
  )
)
